# KnivesDualLoopingARFG.net
KiCad netlist of a schematic drawn in EAGLE
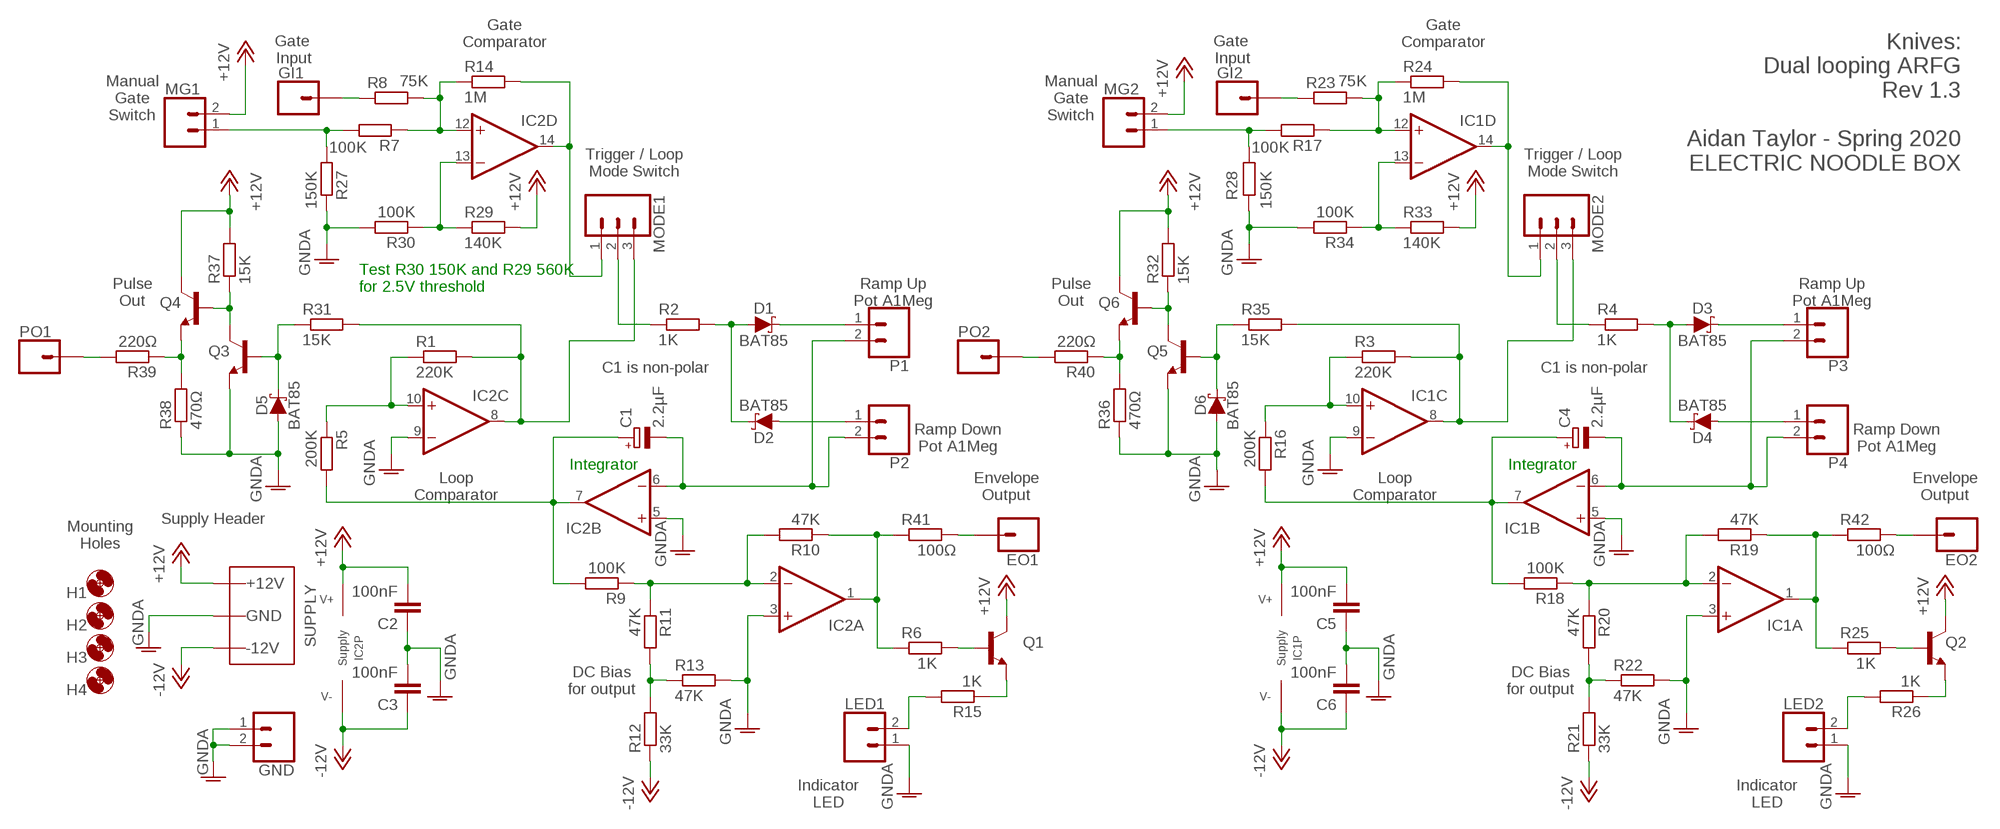
[diagram p0: schematic, sheet 1]

(export (version "E")
  (design (tool "Eeschema 10.0.6"))
  (components
    (comp (ref "C1")
      (value "2.2µF")
      (footprint "eagle-import:E2-5")
      (libsource (lib "eagle-import") (part "CPOL-EUE2-5"))
    )
    (comp (ref "C2")
      (value "100nF")
      (footprint "eagle-import:C050-025X075")
      (libsource (lib "eagle-import") (part "C-EU050-025X075"))
    )
    (comp (ref "C3")
      (value "100nF")
      (footprint "eagle-import:C050-025X075")
      (libsource (lib "eagle-import") (part "C-EU050-025X075"))
    )
    (comp (ref "C4")
      (value "2.2µF")
      (footprint "eagle-import:E2-5")
      (libsource (lib "eagle-import") (part "CPOL-EUE2-5"))
    )
    (comp (ref "C5")
      (value "100nF")
      (footprint "eagle-import:C050-025X075")
      (libsource (lib "eagle-import") (part "C-EU050-025X075"))
    )
    (comp (ref "C6")
      (value "100nF")
      (footprint "eagle-import:C050-025X075")
      (libsource (lib "eagle-import") (part "C-EU050-025X075"))
    )
    (comp (ref "D1")
      (value "BAT85")
      (footprint "eagle-import:DO35-7")
      (libsource (lib "eagle-import") (part "SCHOTTKY_DO35"))
    )
    (comp (ref "D2")
      (value "BAT85")
      (footprint "eagle-import:DO35-7")
      (libsource (lib "eagle-import") (part "SCHOTTKY_DO35"))
    )
    (comp (ref "D3")
      (value "BAT85")
      (footprint "eagle-import:DO35-7")
      (libsource (lib "eagle-import") (part "SCHOTTKY_DO35"))
    )
    (comp (ref "D4")
      (value "BAT85")
      (footprint "eagle-import:DO35-7")
      (libsource (lib "eagle-import") (part "SCHOTTKY_DO35"))
    )
    (comp (ref "D5")
      (value "BAT85")
      (footprint "eagle-import:DO35-7")
      (libsource (lib "eagle-import") (part "SCHOTTKY_DO35"))
    )
    (comp (ref "D6")
      (value "BAT85")
      (footprint "eagle-import:DO35-7")
      (libsource (lib "eagle-import") (part "SCHOTTKY_DO35"))
    )
    (comp (ref "EO1")
      (value "1XWIREPAD")
      (footprint "eagle-import:1X01")
      (libsource (lib "eagle-import") (part "1XWIREPAD"))
    )
    (comp (ref "EO2")
      (value "1XWIREPAD")
      (footprint "eagle-import:1X01")
      (libsource (lib "eagle-import") (part "1XWIREPAD"))
    )
    (comp (ref "GI1")
      (value "1XWIREPAD")
      (footprint "eagle-import:1X01")
      (libsource (lib "eagle-import") (part "1XWIREPAD"))
    )
    (comp (ref "GI2")
      (value "1XWIREPAD")
      (footprint "eagle-import:1X01")
      (libsource (lib "eagle-import") (part "1XWIREPAD"))
    )
    (comp (ref "GND")
      (value "2XWIREPAD")
      (footprint "eagle-import:1X02")
      (libsource (lib "eagle-import") (part "2XWIREPAD"))
    )
    (comp (ref "H1")
      (value "MOUNT-HOLE3.2")
      (footprint "eagle-import:3,2")
      (libsource (lib "eagle-import") (part "MOUNT-HOLE3.2"))
    )
    (comp (ref "H2")
      (value "MOUNT-HOLE3.2")
      (footprint "eagle-import:3,2")
      (libsource (lib "eagle-import") (part "MOUNT-HOLE3.2"))
    )
    (comp (ref "H3")
      (value "MOUNT-HOLE3.2")
      (footprint "eagle-import:3,2")
      (libsource (lib "eagle-import") (part "MOUNT-HOLE3.2"))
    )
    (comp (ref "H4")
      (value "MOUNT-HOLE3.2")
      (footprint "eagle-import:3,2")
      (libsource (lib "eagle-import") (part "MOUNT-HOLE3.2"))
    )
    (comp (ref "IC1")
      (value "TL0X4DIL")
      (footprint "eagle-import:DIL14")
      (libsource (lib "eagle-import") (part "TL0X4DIL"))
    )
    (comp (ref "IC2")
      (value "TL0X4DIL")
      (footprint "eagle-import:DIL14")
      (libsource (lib "eagle-import") (part "TL0X4DIL"))
    )
    (comp (ref "LED1")
      (value "2XWIREPAD")
      (footprint "eagle-import:1X02")
      (libsource (lib "eagle-import") (part "2XWIREPAD"))
    )
    (comp (ref "LED2")
      (value "2XWIREPAD")
      (footprint "eagle-import:1X02")
      (libsource (lib "eagle-import") (part "2XWIREPAD"))
    )
    (comp (ref "MG1")
      (value "2XWIREPAD")
      (footprint "eagle-import:1X02")
      (libsource (lib "eagle-import") (part "2XWIREPAD"))
    )
    (comp (ref "MG2")
      (value "2XWIREPAD")
      (footprint "eagle-import:1X02")
      (libsource (lib "eagle-import") (part "2XWIREPAD"))
    )
    (comp (ref "MODE1")
      (value "3XWIREPAD")
      (footprint "eagle-import:1X03")
      (libsource (lib "eagle-import") (part "3XWIREPAD"))
    )
    (comp (ref "MODE2")
      (value "3XWIREPAD")
      (footprint "eagle-import:1X03")
      (libsource (lib "eagle-import") (part "3XWIREPAD"))
    )
    (comp (ref "P1")
      (value "2XWIREPAD")
      (footprint "eagle-import:1X02")
      (libsource (lib "eagle-import") (part "2XWIREPAD"))
    )
    (comp (ref "P2")
      (value "2XWIREPAD")
      (footprint "eagle-import:1X02")
      (libsource (lib "eagle-import") (part "2XWIREPAD"))
    )
    (comp (ref "P3")
      (value "2XWIREPAD")
      (footprint "eagle-import:1X02")
      (libsource (lib "eagle-import") (part "2XWIREPAD"))
    )
    (comp (ref "P4")
      (value "2XWIREPAD")
      (footprint "eagle-import:1X02")
      (libsource (lib "eagle-import") (part "2XWIREPAD"))
    )
    (comp (ref "PO1")
      (value "1XWIREPAD")
      (footprint "eagle-import:1X01")
      (libsource (lib "eagle-import") (part "1XWIREPAD"))
    )
    (comp (ref "PO2")
      (value "1XWIREPAD")
      (footprint "eagle-import:1X01")
      (libsource (lib "eagle-import") (part "1XWIREPAD"))
    )
    (comp (ref "Q1")
      (value "2N3904")
      (footprint "eagle-import:TO92")
      (libsource (lib "eagle-import") (part "2N3904"))
    )
    (comp (ref "Q2")
      (value "2N3904")
      (footprint "eagle-import:TO92")
      (libsource (lib "eagle-import") (part "2N3904"))
    )
    (comp (ref "Q3")
      (value "2N3904")
      (footprint "eagle-import:TO92")
      (libsource (lib "eagle-import") (part "2N3904"))
    )
    (comp (ref "Q4")
      (value "2N3904")
      (footprint "eagle-import:TO92")
      (libsource (lib "eagle-import") (part "2N3904"))
    )
    (comp (ref "Q5")
      (value "2N3904")
      (footprint "eagle-import:TO92")
      (libsource (lib "eagle-import") (part "2N3904"))
    )
    (comp (ref "Q6")
      (value "2N3904")
      (footprint "eagle-import:TO92")
      (libsource (lib "eagle-import") (part "2N3904"))
    )
    (comp (ref "R1")
      (value "220K")
      (footprint "eagle-import:0207_10")
      (libsource (lib "eagle-import") (part "R-EU_0207/10"))
    )
    (comp (ref "R2")
      (value "1K")
      (footprint "eagle-import:0207_10")
      (libsource (lib "eagle-import") (part "R-EU_0207/10"))
    )
    (comp (ref "R3")
      (value "220K")
      (footprint "eagle-import:0207_10")
      (libsource (lib "eagle-import") (part "R-EU_0207/10"))
    )
    (comp (ref "R4")
      (value "1K")
      (footprint "eagle-import:0207_10")
      (libsource (lib "eagle-import") (part "R-EU_0207/10"))
    )
    (comp (ref "R5")
      (value "200K")
      (footprint "eagle-import:0207_10")
      (libsource (lib "eagle-import") (part "R-EU_0207/10"))
    )
    (comp (ref "R6")
      (value "1K")
      (footprint "eagle-import:0207_10")
      (libsource (lib "eagle-import") (part "R-EU_0207/10"))
    )
    (comp (ref "R7")
      (value "100K")
      (footprint "eagle-import:0207_10")
      (libsource (lib "eagle-import") (part "R-EU_0207/10"))
    )
    (comp (ref "R8")
      (value "75K")
      (footprint "eagle-import:0207_10")
      (libsource (lib "eagle-import") (part "R-EU_0207/10"))
    )
    (comp (ref "R9")
      (value "100K")
      (footprint "eagle-import:0207_10")
      (libsource (lib "eagle-import") (part "R-EU_0207/10"))
    )
    (comp (ref "R10")
      (value "47K")
      (footprint "eagle-import:0207_10")
      (libsource (lib "eagle-import") (part "R-EU_0207/10"))
    )
    (comp (ref "R11")
      (value "47K")
      (footprint "eagle-import:0207_10")
      (libsource (lib "eagle-import") (part "R-EU_0207/10"))
    )
    (comp (ref "R12")
      (value "33K")
      (footprint "eagle-import:0207_10")
      (libsource (lib "eagle-import") (part "R-EU_0207/10"))
    )
    (comp (ref "R13")
      (value "47K")
      (footprint "eagle-import:0207_10")
      (libsource (lib "eagle-import") (part "R-EU_0207/10"))
    )
    (comp (ref "R14")
      (value "1M")
      (footprint "eagle-import:0207_10")
      (libsource (lib "eagle-import") (part "R-EU_0207/10"))
    )
    (comp (ref "R15")
      (value "1K")
      (footprint "eagle-import:0207_10")
      (libsource (lib "eagle-import") (part "R-EU_0207/10"))
    )
    (comp (ref "R16")
      (value "200K")
      (footprint "eagle-import:0207_10")
      (libsource (lib "eagle-import") (part "R-EU_0207/10"))
    )
    (comp (ref "R17")
      (value "100K")
      (footprint "eagle-import:0207_10")
      (libsource (lib "eagle-import") (part "R-EU_0207/10"))
    )
    (comp (ref "R18")
      (value "100K")
      (footprint "eagle-import:0207_10")
      (libsource (lib "eagle-import") (part "R-EU_0207/10"))
    )
    (comp (ref "R19")
      (value "47K")
      (footprint "eagle-import:0207_10")
      (libsource (lib "eagle-import") (part "R-EU_0207/10"))
    )
    (comp (ref "R20")
      (value "47K")
      (footprint "eagle-import:0207_10")
      (libsource (lib "eagle-import") (part "R-EU_0207/10"))
    )
    (comp (ref "R21")
      (value "33K")
      (footprint "eagle-import:0207_10")
      (libsource (lib "eagle-import") (part "R-EU_0207/10"))
    )
    (comp (ref "R22")
      (value "47K")
      (footprint "eagle-import:0207_10")
      (libsource (lib "eagle-import") (part "R-EU_0207/10"))
    )
    (comp (ref "R23")
      (value "75K")
      (footprint "eagle-import:0207_10")
      (libsource (lib "eagle-import") (part "R-EU_0207/10"))
    )
    (comp (ref "R24")
      (value "1M")
      (footprint "eagle-import:0207_10")
      (libsource (lib "eagle-import") (part "R-EU_0207/10"))
    )
    (comp (ref "R25")
      (value "1K")
      (footprint "eagle-import:0207_10")
      (libsource (lib "eagle-import") (part "R-EU_0207/10"))
    )
    (comp (ref "R26")
      (value "1K")
      (footprint "eagle-import:0207_10")
      (libsource (lib "eagle-import") (part "R-EU_0207/10"))
    )
    (comp (ref "R27")
      (value "150K")
      (footprint "eagle-import:0207_10")
      (libsource (lib "eagle-import") (part "R-EU_0207/10"))
    )
    (comp (ref "R28")
      (value "150K")
      (footprint "eagle-import:0207_10")
      (libsource (lib "eagle-import") (part "R-EU_0207/10"))
    )
    (comp (ref "R29")
      (value "140K")
      (footprint "eagle-import:0207_10")
      (libsource (lib "eagle-import") (part "R-EU_0207/10"))
    )
    (comp (ref "R30")
      (value "100K")
      (footprint "eagle-import:0207_10")
      (libsource (lib "eagle-import") (part "R-EU_0207/10"))
    )
    (comp (ref "R31")
      (value "15K")
      (footprint "eagle-import:0207_10")
      (libsource (lib "eagle-import") (part "R-EU_0207/10"))
    )
    (comp (ref "R32")
      (value "15K")
      (footprint "eagle-import:0207_10")
      (libsource (lib "eagle-import") (part "R-EU_0207/10"))
    )
    (comp (ref "R33")
      (value "140K")
      (footprint "eagle-import:0207_10")
      (libsource (lib "eagle-import") (part "R-EU_0207/10"))
    )
    (comp (ref "R34")
      (value "100K")
      (footprint "eagle-import:0207_10")
      (libsource (lib "eagle-import") (part "R-EU_0207/10"))
    )
    (comp (ref "R35")
      (value "15K")
      (footprint "eagle-import:0207_10")
      (libsource (lib "eagle-import") (part "R-EU_0207/10"))
    )
    (comp (ref "R36")
      (value "470Ω")
      (footprint "eagle-import:0207_10")
      (libsource (lib "eagle-import") (part "R-EU_0207/10"))
    )
    (comp (ref "R37")
      (value "15K")
      (footprint "eagle-import:0207_10")
      (libsource (lib "eagle-import") (part "R-EU_0207/10"))
    )
    (comp (ref "R38")
      (value "470Ω")
      (footprint "eagle-import:0207_10")
      (libsource (lib "eagle-import") (part "R-EU_0207/10"))
    )
    (comp (ref "R39")
      (value "220Ω")
      (footprint "eagle-import:0207_10")
      (libsource (lib "eagle-import") (part "R-EU_0207/10"))
    )
    (comp (ref "R40")
      (value "220Ω")
      (footprint "eagle-import:0207_10")
      (libsource (lib "eagle-import") (part "R-EU_0207/10"))
    )
    (comp (ref "R41")
      (value "100Ω")
      (footprint "eagle-import:0207_10")
      (libsource (lib "eagle-import") (part "R-EU_0207/10"))
    )
    (comp (ref "R42")
      (value "100Ω")
      (footprint "eagle-import:0207_10")
      (libsource (lib "eagle-import") (part "R-EU_0207/10"))
    )
    (comp (ref "WP1")
      (value "COMBO_SUPPLY_HEADER")
      (footprint "eagle-import:COMBINED_POWER")
      (libsource (lib "eagle-import") (part "COMBO_SUPPLY_HEADER"))
    )
  )
  (nets
    (net (code "1") (name "+12V") (class "Default")
      (node (ref "C2") (pin "2") (pinfunction "2_2") (pintype "passive"))
      (node (ref "C5") (pin "2") (pinfunction "2_2") (pintype "passive"))
      (node (ref "IC1") (pin "4") (pinfunction "V+_4") (pintype "bidirectional"))
      (node (ref "IC2") (pin "4") (pinfunction "V+_4") (pintype "bidirectional"))
      (node (ref "MG1") (pin "2") (pinfunction "2_2") (pintype "passive"))
      (node (ref "MG2") (pin "2") (pinfunction "2_2") (pintype "passive"))
      (node (ref "Q1") (pin "1") (pinfunction "C_1") (pintype "passive"))
      (node (ref "Q2") (pin "1") (pinfunction "C_1") (pintype "passive"))
      (node (ref "Q4") (pin "1") (pinfunction "C_1") (pintype "passive"))
      (node (ref "Q6") (pin "1") (pinfunction "C_1") (pintype "passive"))
      (node (ref "R29") (pin "2") (pinfunction "2_2") (pintype "passive"))
      (node (ref "R32") (pin "2") (pinfunction "2_2") (pintype "passive"))
      (node (ref "R33") (pin "2") (pinfunction "2_2") (pintype "passive"))
      (node (ref "R37") (pin "2") (pinfunction "2_2") (pintype "passive"))
      (node (ref "WP1") (pin "V+1") (pinfunction "V++_V+1") (pintype "power_in"))
      (node (ref "WP1") (pin "V+2") (pinfunction "V++_V+2") (pintype "power_in"))
      (node (ref "WP1") (pin "V+3") (pinfunction "V++_V+3") (pintype "power_in"))
    )
    (net (code "2") (name "-12V") (class "Default")
      (node (ref "C3") (pin "1") (pinfunction "1_1") (pintype "passive"))
      (node (ref "C6") (pin "1") (pinfunction "1_1") (pintype "passive"))
      (node (ref "IC1") (pin "11") (pinfunction "V-_11") (pintype "bidirectional"))
      (node (ref "IC2") (pin "11") (pinfunction "V-_11") (pintype "bidirectional"))
      (node (ref "R12") (pin "1") (pinfunction "1_1") (pintype "passive"))
      (node (ref "R21") (pin "1") (pinfunction "1_1") (pintype "passive"))
      (node (ref "WP1") (pin "V-1") (pinfunction "V--_V-1") (pintype "power_in"))
      (node (ref "WP1") (pin "V-2") (pinfunction "V--_V-2") (pintype "power_in"))
      (node (ref "WP1") (pin "V-3") (pinfunction "V--_V-3") (pintype "power_in"))
    )
    (net (code "3") (name "GNDA") (class "Default")
      (node (ref "C2") (pin "1") (pinfunction "1_1") (pintype "passive"))
      (node (ref "C3") (pin "2") (pinfunction "2_2") (pintype "passive"))
      (node (ref "C5") (pin "1") (pinfunction "1_1") (pintype "passive"))
      (node (ref "C6") (pin "2") (pinfunction "2_2") (pintype "passive"))
      (node (ref "D5") (pin "A") (pinfunction "A_A") (pintype "passive"))
      (node (ref "D6") (pin "A") (pinfunction "A_A") (pintype "passive"))
      (node (ref "GND") (pin "1") (pinfunction "1_1") (pintype "passive"))
      (node (ref "GND") (pin "2") (pinfunction "2_2") (pintype "passive"))
      (node (ref "IC1") (pin "3") (pinfunction "+IN_3") (pintype "input"))
      (node (ref "IC1") (pin "5") (pinfunction "+IN_5") (pintype "input"))
      (node (ref "IC1") (pin "9") (pinfunction "-IN_9") (pintype "input"))
      (node (ref "IC2") (pin "3") (pinfunction "+IN_3") (pintype "input"))
      (node (ref "IC2") (pin "5") (pinfunction "+IN_5") (pintype "input"))
      (node (ref "IC2") (pin "9") (pinfunction "-IN_9") (pintype "input"))
      (node (ref "LED1") (pin "1") (pinfunction "1_1") (pintype "passive"))
      (node (ref "LED2") (pin "1") (pinfunction "1_1") (pintype "passive"))
      (node (ref "Q3") (pin "3") (pinfunction "E_3") (pintype "passive"))
      (node (ref "Q5") (pin "3") (pinfunction "E_3") (pintype "passive"))
      (node (ref "R13") (pin "2") (pinfunction "2_2") (pintype "passive"))
      (node (ref "R22") (pin "2") (pinfunction "2_2") (pintype "passive"))
      (node (ref "R27") (pin "2") (pinfunction "2_2") (pintype "passive"))
      (node (ref "R28") (pin "2") (pinfunction "2_2") (pintype "passive"))
      (node (ref "R30") (pin "2") (pinfunction "2_2") (pintype "passive"))
      (node (ref "R34") (pin "2") (pinfunction "2_2") (pintype "passive"))
      (node (ref "R36") (pin "1") (pinfunction "1_1") (pintype "passive"))
      (node (ref "R38") (pin "1") (pinfunction "1_1") (pintype "passive"))
      (node (ref "WP1") (pin "GND1") (pinfunction "AGND_GND1") (pintype "power_in"))
      (node (ref "WP1") (pin "GND2") (pinfunction "AGND_GND2") (pintype "power_in"))
      (node (ref "WP1") (pin "GND3") (pinfunction "AGND_GND3") (pintype "power_in"))
      (node (ref "WP1") (pin "GND4") (pinfunction "AGND_GND4") (pintype "power_in"))
      (node (ref "WP1") (pin "GND5") (pinfunction "AGND_GND5") (pintype "power_in"))
      (node (ref "WP1") (pin "GND6") (pinfunction "AGND_GND6") (pintype "power_in"))
      (node (ref "WP1") (pin "GND7") (pinfunction "AGND_GND7") (pintype "power_in"))
      (node (ref "WP1") (pin "GND8") (pinfunction "AGND_GND8") (pintype "power_in"))
    )
    (net (code "4") (name "Net-(D1-PadA)") (class "Default")
      (node (ref "D1") (pin "A") (pinfunction "A_A") (pintype "passive"))
      (node (ref "D2") (pin "C") (pinfunction "C_C") (pintype "passive"))
      (node (ref "R2") (pin "2") (pinfunction "2_2") (pintype "passive"))
    )
    (net (code "5") (name "Net-(D1-PadC)") (class "Default")
      (node (ref "D1") (pin "C") (pinfunction "C_C") (pintype "passive"))
      (node (ref "P1") (pin "1") (pinfunction "1_1") (pintype "passive"))
    )
    (net (code "6") (name "Net-(D2-PadA)") (class "Default")
      (node (ref "D2") (pin "A") (pinfunction "A_A") (pintype "passive"))
      (node (ref "P2") (pin "1") (pinfunction "1_1") (pintype "passive"))
    )
    (net (code "7") (name "Net-(D3-PadA)") (class "Default")
      (node (ref "D3") (pin "A") (pinfunction "A_A") (pintype "passive"))
      (node (ref "D4") (pin "C") (pinfunction "C_C") (pintype "passive"))
      (node (ref "R4") (pin "2") (pinfunction "2_2") (pintype "passive"))
    )
    (net (code "8") (name "Net-(D3-PadC)") (class "Default")
      (node (ref "D3") (pin "C") (pinfunction "C_C") (pintype "passive"))
      (node (ref "P3") (pin "1") (pinfunction "1_1") (pintype "passive"))
    )
    (net (code "9") (name "Net-(D4-PadA)") (class "Default")
      (node (ref "D4") (pin "A") (pinfunction "A_A") (pintype "passive"))
      (node (ref "P4") (pin "1") (pinfunction "1_1") (pintype "passive"))
    )
    (net (code "10") (name "Net-(EO1-Pad1)") (class "Default")
      (node (ref "EO1") (pin "1") (pinfunction "1_1") (pintype "passive"))
      (node (ref "R41") (pin "2") (pinfunction "2_2") (pintype "passive"))
    )
    (net (code "11") (name "Net-(EO2-Pad1)") (class "Default")
      (node (ref "EO2") (pin "1") (pinfunction "1_1") (pintype "passive"))
      (node (ref "R42") (pin "2") (pinfunction "2_2") (pintype "passive"))
    )
    (net (code "12") (name "Net-(GI1-Pad1)") (class "Default")
      (node (ref "GI1") (pin "1") (pinfunction "1_1") (pintype "passive"))
      (node (ref "R8") (pin "1") (pinfunction "1_1") (pintype "passive"))
    )
    (net (code "13") (name "Net-(GI2-Pad1)") (class "Default")
      (node (ref "GI2") (pin "1") (pinfunction "1_1") (pintype "passive"))
      (node (ref "R23") (pin "1") (pinfunction "1_1") (pintype "passive"))
    )
    (net (code "14") (name "Net-(IC1A--IN)") (class "Default")
      (node (ref "IC1") (pin "2") (pinfunction "-IN_2") (pintype "input"))
      (node (ref "R18") (pin "1") (pinfunction "1_1") (pintype "passive"))
      (node (ref "R19") (pin "2") (pinfunction "2_2") (pintype "passive"))
      (node (ref "R20") (pin "1") (pinfunction "1_1") (pintype "passive"))
    )
    (net (code "15") (name "Net-(IC1A-OUT)") (class "Default")
      (node (ref "IC1") (pin "1") (pinfunction "OUT_1") (pintype "output"))
      (node (ref "R19") (pin "1") (pinfunction "1_1") (pintype "passive"))
      (node (ref "R25") (pin "1") (pinfunction "1_1") (pintype "passive"))
      (node (ref "R42") (pin "1") (pinfunction "1_1") (pintype "passive"))
    )
    (net (code "16") (name "Net-(IC1B--IN)") (class "Default")
      (node (ref "C4") (pin "-") (pinfunction "-_-") (pintype "passive"))
      (node (ref "IC1") (pin "6") (pinfunction "-IN_6") (pintype "input"))
      (node (ref "P3") (pin "2") (pinfunction "2_2") (pintype "passive"))
      (node (ref "P4") (pin "2") (pinfunction "2_2") (pintype "passive"))
    )
    (net (code "17") (name "Net-(IC1B-OUT)") (class "Default")
      (node (ref "C4") (pin "+") (pinfunction "+_+") (pintype "passive"))
      (node (ref "IC1") (pin "7") (pinfunction "OUT_7") (pintype "output"))
      (node (ref "R16") (pin "2") (pinfunction "2_2") (pintype "passive"))
      (node (ref "R18") (pin "2") (pinfunction "2_2") (pintype "passive"))
    )
    (net (code "18") (name "Net-(IC1C-+IN)") (class "Default")
      (node (ref "IC1") (pin "10") (pinfunction "+IN_10") (pintype "input"))
      (node (ref "R16") (pin "1") (pinfunction "1_1") (pintype "passive"))
      (node (ref "R3") (pin "1") (pinfunction "1_1") (pintype "passive"))
    )
    (net (code "19") (name "Net-(IC1C-OUT)") (class "Default")
      (node (ref "IC1") (pin "8") (pinfunction "OUT_8") (pintype "output"))
      (node (ref "MODE2") (pin "3") (pinfunction "3_3") (pintype "passive"))
      (node (ref "R3") (pin "2") (pinfunction "2_2") (pintype "passive"))
      (node (ref "R35") (pin "2") (pinfunction "2_2") (pintype "passive"))
    )
    (net (code "20") (name "Net-(IC1D-+IN)") (class "Default")
      (node (ref "IC1") (pin "12") (pinfunction "+IN_12") (pintype "input"))
      (node (ref "R17") (pin "1") (pinfunction "1_1") (pintype "passive"))
      (node (ref "R23") (pin "2") (pinfunction "2_2") (pintype "passive"))
      (node (ref "R24") (pin "1") (pinfunction "1_1") (pintype "passive"))
    )
    (net (code "21") (name "Net-(IC1D--IN)") (class "Default")
      (node (ref "IC1") (pin "13") (pinfunction "-IN_13") (pintype "input"))
      (node (ref "R33") (pin "1") (pinfunction "1_1") (pintype "passive"))
      (node (ref "R34") (pin "1") (pinfunction "1_1") (pintype "passive"))
    )
    (net (code "22") (name "Net-(IC1D-OUT)") (class "Default")
      (node (ref "IC1") (pin "14") (pinfunction "OUT_14") (pintype "output"))
      (node (ref "MODE2") (pin "1") (pinfunction "1_1") (pintype "passive"))
      (node (ref "R24") (pin "2") (pinfunction "2_2") (pintype "passive"))
    )
    (net (code "23") (name "Net-(IC2A--IN)") (class "Default")
      (node (ref "IC2") (pin "2") (pinfunction "-IN_2") (pintype "input"))
      (node (ref "R10") (pin "2") (pinfunction "2_2") (pintype "passive"))
      (node (ref "R11") (pin "1") (pinfunction "1_1") (pintype "passive"))
      (node (ref "R9") (pin "1") (pinfunction "1_1") (pintype "passive"))
    )
    (net (code "24") (name "Net-(IC2A-OUT)") (class "Default")
      (node (ref "IC2") (pin "1") (pinfunction "OUT_1") (pintype "output"))
      (node (ref "R10") (pin "1") (pinfunction "1_1") (pintype "passive"))
      (node (ref "R41") (pin "1") (pinfunction "1_1") (pintype "passive"))
      (node (ref "R6") (pin "1") (pinfunction "1_1") (pintype "passive"))
    )
    (net (code "25") (name "Net-(IC2B--IN)") (class "Default")
      (node (ref "C1") (pin "-") (pinfunction "-_-") (pintype "passive"))
      (node (ref "IC2") (pin "6") (pinfunction "-IN_6") (pintype "input"))
      (node (ref "P1") (pin "2") (pinfunction "2_2") (pintype "passive"))
      (node (ref "P2") (pin "2") (pinfunction "2_2") (pintype "passive"))
    )
    (net (code "26") (name "Net-(IC2B-OUT)") (class "Default")
      (node (ref "C1") (pin "+") (pinfunction "+_+") (pintype "passive"))
      (node (ref "IC2") (pin "7") (pinfunction "OUT_7") (pintype "output"))
      (node (ref "R5") (pin "2") (pinfunction "2_2") (pintype "passive"))
      (node (ref "R9") (pin "2") (pinfunction "2_2") (pintype "passive"))
    )
    (net (code "27") (name "Net-(IC2C-+IN)") (class "Default")
      (node (ref "IC2") (pin "10") (pinfunction "+IN_10") (pintype "input"))
      (node (ref "R1") (pin "1") (pinfunction "1_1") (pintype "passive"))
      (node (ref "R5") (pin "1") (pinfunction "1_1") (pintype "passive"))
    )
    (net (code "28") (name "Net-(IC2C-OUT)") (class "Default")
      (node (ref "IC2") (pin "8") (pinfunction "OUT_8") (pintype "output"))
      (node (ref "MODE1") (pin "3") (pinfunction "3_3") (pintype "passive"))
      (node (ref "R1") (pin "2") (pinfunction "2_2") (pintype "passive"))
      (node (ref "R31") (pin "2") (pinfunction "2_2") (pintype "passive"))
    )
    (net (code "29") (name "Net-(IC2D-+IN)") (class "Default")
      (node (ref "IC2") (pin "12") (pinfunction "+IN_12") (pintype "input"))
      (node (ref "R14") (pin "1") (pinfunction "1_1") (pintype "passive"))
      (node (ref "R7") (pin "1") (pinfunction "1_1") (pintype "passive"))
      (node (ref "R8") (pin "2") (pinfunction "2_2") (pintype "passive"))
    )
    (net (code "30") (name "Net-(IC2D--IN)") (class "Default")
      (node (ref "IC2") (pin "13") (pinfunction "-IN_13") (pintype "input"))
      (node (ref "R29") (pin "1") (pinfunction "1_1") (pintype "passive"))
      (node (ref "R30") (pin "1") (pinfunction "1_1") (pintype "passive"))
    )
    (net (code "31") (name "Net-(IC2D-OUT)") (class "Default")
      (node (ref "IC2") (pin "14") (pinfunction "OUT_14") (pintype "output"))
      (node (ref "MODE1") (pin "1") (pinfunction "1_1") (pintype "passive"))
      (node (ref "R14") (pin "2") (pinfunction "2_2") (pintype "passive"))
    )
    (net (code "32") (name "Net-(LED1-Pad2)") (class "Default")
      (node (ref "LED1") (pin "2") (pinfunction "2_2") (pintype "passive"))
      (node (ref "R15") (pin "2") (pinfunction "2_2") (pintype "passive"))
    )
    (net (code "33") (name "Net-(LED2-Pad2)") (class "Default")
      (node (ref "LED2") (pin "2") (pinfunction "2_2") (pintype "passive"))
      (node (ref "R26") (pin "2") (pinfunction "2_2") (pintype "passive"))
    )
    (net (code "34") (name "Net-(MG1-Pad1)") (class "Default")
      (node (ref "MG1") (pin "1") (pinfunction "1_1") (pintype "passive"))
      (node (ref "R27") (pin "1") (pinfunction "1_1") (pintype "passive"))
      (node (ref "R7") (pin "2") (pinfunction "2_2") (pintype "passive"))
    )
    (net (code "35") (name "Net-(MG2-Pad1)") (class "Default")
      (node (ref "MG2") (pin "1") (pinfunction "1_1") (pintype "passive"))
      (node (ref "R17") (pin "2") (pinfunction "2_2") (pintype "passive"))
      (node (ref "R28") (pin "1") (pinfunction "1_1") (pintype "passive"))
    )
    (net (code "36") (name "Net-(MODE1-Pad2)") (class "Default")
      (node (ref "MODE1") (pin "2") (pinfunction "2_2") (pintype "passive"))
      (node (ref "R2") (pin "1") (pinfunction "1_1") (pintype "passive"))
    )
    (net (code "37") (name "Net-(MODE2-Pad2)") (class "Default")
      (node (ref "MODE2") (pin "2") (pinfunction "2_2") (pintype "passive"))
      (node (ref "R4") (pin "1") (pinfunction "1_1") (pintype "passive"))
    )
    (net (code "38") (name "Net-(PO1-Pad1)") (class "Default")
      (node (ref "PO1") (pin "1") (pinfunction "1_1") (pintype "passive"))
      (node (ref "R39") (pin "2") (pinfunction "2_2") (pintype "passive"))
    )
    (net (code "39") (name "Net-(PO2-Pad1)") (class "Default")
      (node (ref "PO2") (pin "1") (pinfunction "1_1") (pintype "passive"))
      (node (ref "R40") (pin "2") (pinfunction "2_2") (pintype "passive"))
    )
    (net (code "40") (name "Net-(Q1-B)") (class "Default")
      (node (ref "Q1") (pin "2") (pinfunction "B_2") (pintype "passive"))
      (node (ref "R6") (pin "2") (pinfunction "2_2") (pintype "passive"))
    )
    (net (code "41") (name "Net-(Q1-E)") (class "Default")
      (node (ref "Q1") (pin "3") (pinfunction "E_3") (pintype "passive"))
      (node (ref "R15") (pin "1") (pinfunction "1_1") (pintype "passive"))
    )
    (net (code "42") (name "Net-(Q2-B)") (class "Default")
      (node (ref "Q2") (pin "2") (pinfunction "B_2") (pintype "passive"))
      (node (ref "R25") (pin "2") (pinfunction "2_2") (pintype "passive"))
    )
    (net (code "43") (name "Net-(Q2-E)") (class "Default")
      (node (ref "Q2") (pin "3") (pinfunction "E_3") (pintype "passive"))
      (node (ref "R26") (pin "1") (pinfunction "1_1") (pintype "passive"))
    )
    (net (code "44") (name "Net-(Q3-B)") (class "Default")
      (node (ref "D5") (pin "C") (pinfunction "C_C") (pintype "passive"))
      (node (ref "Q3") (pin "2") (pinfunction "B_2") (pintype "passive"))
      (node (ref "R31") (pin "1") (pinfunction "1_1") (pintype "passive"))
    )
    (net (code "45") (name "Net-(Q3-C)") (class "Default")
      (node (ref "Q3") (pin "1") (pinfunction "C_1") (pintype "passive"))
      (node (ref "Q4") (pin "2") (pinfunction "B_2") (pintype "passive"))
      (node (ref "R37") (pin "1") (pinfunction "1_1") (pintype "passive"))
    )
    (net (code "46") (name "Net-(Q4-E)") (class "Default")
      (node (ref "Q4") (pin "3") (pinfunction "E_3") (pintype "passive"))
      (node (ref "R38") (pin "2") (pinfunction "2_2") (pintype "passive"))
      (node (ref "R39") (pin "1") (pinfunction "1_1") (pintype "passive"))
    )
    (net (code "47") (name "Net-(Q5-B)") (class "Default")
      (node (ref "D6") (pin "C") (pinfunction "C_C") (pintype "passive"))
      (node (ref "Q5") (pin "2") (pinfunction "B_2") (pintype "passive"))
      (node (ref "R35") (pin "1") (pinfunction "1_1") (pintype "passive"))
    )
    (net (code "48") (name "Net-(Q5-C)") (class "Default")
      (node (ref "Q5") (pin "1") (pinfunction "C_1") (pintype "passive"))
      (node (ref "Q6") (pin "2") (pinfunction "B_2") (pintype "passive"))
      (node (ref "R32") (pin "1") (pinfunction "1_1") (pintype "passive"))
    )
    (net (code "49") (name "Net-(Q6-E)") (class "Default")
      (node (ref "Q6") (pin "3") (pinfunction "E_3") (pintype "passive"))
      (node (ref "R36") (pin "2") (pinfunction "2_2") (pintype "passive"))
      (node (ref "R40") (pin "1") (pinfunction "1_1") (pintype "passive"))
    )
    (net (code "50") (name "Net-(R11-Pad2)") (class "Default")
      (node (ref "R11") (pin "2") (pinfunction "2_2") (pintype "passive"))
      (node (ref "R12") (pin "2") (pinfunction "2_2") (pintype "passive"))
      (node (ref "R13") (pin "1") (pinfunction "1_1") (pintype "passive"))
    )
    (net (code "51") (name "Net-(R20-Pad2)") (class "Default")
      (node (ref "R20") (pin "2") (pinfunction "2_2") (pintype "passive"))
      (node (ref "R21") (pin "2") (pinfunction "2_2") (pintype "passive"))
      (node (ref "R22") (pin "1") (pinfunction "1_1") (pintype "passive"))
    )
  )
)
